# ir-tara-smd-ttp223.net
KiCad netlist of a schematic drawn in Altium Designer
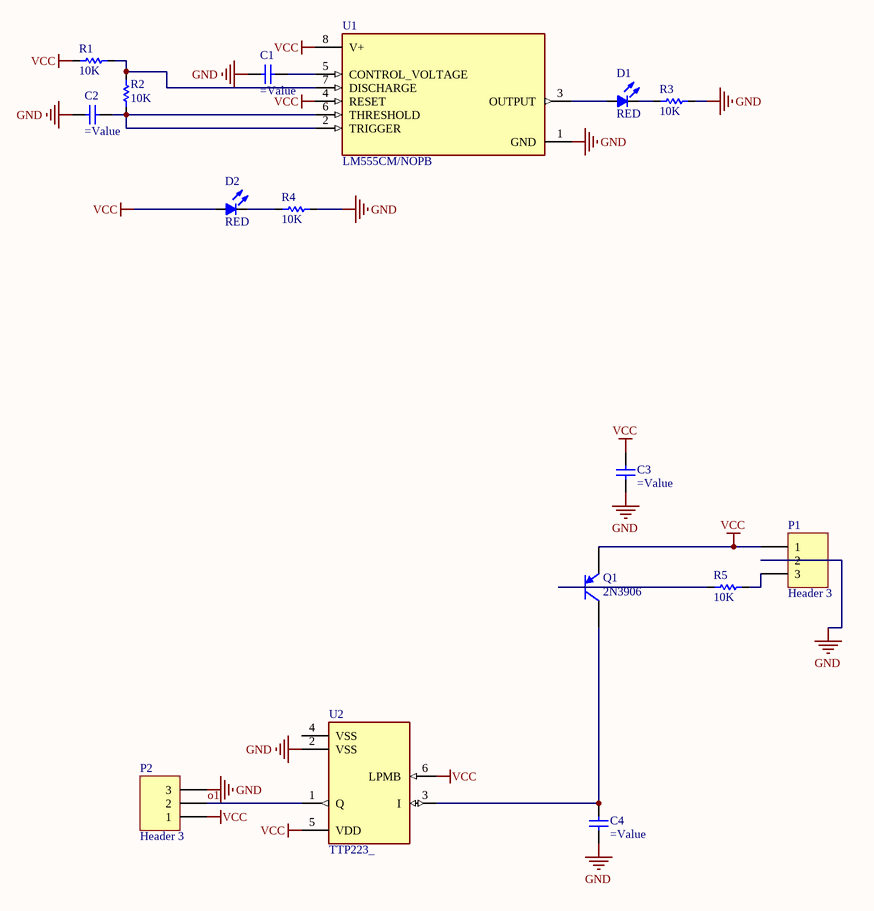
[diagram p0: ir-tara-smd-ttp223.SchDoc]

(export (version "E")
  (design (tool "Eeschema 10.0.6"))
  (components
    (comp (ref "C1")
      (value "~")
      (footprint "CAP 0805")
      (description "Capacitor")
      (libsource (lib "AltiumLib1") (part "Capacitor"))
    )
    (comp (ref "C2")
      (value "~")
      (footprint "CAP 0805")
      (description "Capacitor")
      (libsource (lib "AltiumLib1") (part "Capacitor"))
    )
    (comp (ref "C3")
      (value "~")
      (footprint "CAP 0805")
      (description "Capacitor")
      (libsource (lib "AltiumLib1") (part "Capacitor"))
    )
    (comp (ref "C4")
      (value "~")
      (footprint "CAP 1206")
      (description "Capacitor")
      (libsource (lib "AltiumLib1") (part "Capacitor"))
    )
    (comp (ref "D1")
      (value "MODEL")
      (footprint "LED-5mm")
      (description "Typical LED")
      (fields (field (name "COLOR") "RED"))
      (libsource (lib "AltiumLib1") (part "LED 5mm"))
    )
    (comp (ref "D2")
      (value "MODEL")
      (footprint "LED-5mm")
      (description "Typical LED")
      (fields (field (name "COLOR") "RED"))
      (libsource (lib "AltiumLib1") (part "LED 5mm"))
    )
    (comp (ref "P1")
      (value "Header 3")
      (footprint "HDR1X3")
      (description "Header, 3-Pin")
      (fields (field (name "PUBLISHER") "Altium Limited"))
      (libsource (lib "Miscellaneous Connectors") (part "Header 3"))
    )
    (comp (ref "P2")
      (value "Header 3")
      (footprint "HDR1X3")
      (description "Header, 3-Pin")
      (fields (field (name "PUBLISHER") "Altium Limited"))
      (libsource (lib "") (part "Header 3_1"))
    )
    (comp (ref "Q1")
      (value "2N3906")
      (footprint "MMBT3904-TP:SOT23-3")
      (description "PNP General Purpose Amplifier")
      (fields (field (name "PUBLISHER") "Altium Limited"))
      (libsource (lib "Miscellaneous Devices") (part "2N3906"))
    )
    (comp (ref "R1")
      (value "10K")
      (footprint "RES 0805 (2012X06L)")
      (description "Resistor")
      (fields (field (name "TOLERANCE") "5%") (field (name "POWER") "1/4 W"))
      (libsource (lib "AltiumLib1") (part "Resistor"))
    )
    (comp (ref "R2")
      (value "10K")
      (footprint "RES 0805 (2012X06L)")
      (description "Resistor")
      (fields (field (name "TOLERANCE") "5%") (field (name "POWER") "1/4 W"))
      (libsource (lib "AltiumLib1") (part "Resistor"))
    )
    (comp (ref "R3")
      (value "10K")
      (footprint "RES 0805 (2012X06L)")
      (description "Resistor")
      (fields (field (name "TOLERANCE") "5%") (field (name "POWER") "1/4 W"))
      (libsource (lib "AltiumLib1") (part "Resistor"))
    )
    (comp (ref "R4")
      (value "10K")
      (footprint "RES 1206 (3216X08L)")
      (description "Resistor")
      (fields (field (name "TOLERANCE") "5%") (field (name "POWER") "1/4 W"))
      (libsource (lib "AltiumLib1") (part "Resistor"))
    )
    (comp (ref "R5")
      (value "10K")
      (footprint "RES 0805 (2012X06L)")
      (description "Resistor")
      (fields (field (name "TOLERANCE") "5%") (field (name "POWER") "1/4 W"))
      (libsource (lib "AltiumLib1") (part "Resistor"))
    )
    (comp (ref "U1")
      (value "LM555CM/NOPB")
      (footprint "SOIC127P599X175-8N")
      (description "Highly Stable 555 Timer 8-SOIC 0 to 70")
      (libsource (lib "LM555CM_NOPB") (part "LM555CM/NOPB"))
    )
    (comp (ref "U2")
      (value "TTP223_")
      (footprint "SOT95P285X126-6N")
      (fields (field (name "MP") "TTP223") (field (name "MF") "KOA Speer"))
      (libsource (lib "TTP223_") (part "TTP223_"))
    )
  )
  (nets
    (net (code "1") (name "/o1") (class "Default")
      (node (ref "P2") (pin "2") (pinfunction "2_2") (pintype "passive"))
      (node (ref "U2") (pin "1") (pinfunction "Q_1") (pintype "output"))
    )
    (net (code "2") (name "GND") (class "Default")
      (node (ref "C1") (pin "2") (pinfunction "-_2") (pintype "passive"))
      (node (ref "C2") (pin "2") (pinfunction "-_2") (pintype "passive"))
      (node (ref "C3") (pin "2") (pinfunction "-_2") (pintype "passive"))
      (node (ref "C4") (pin "2") (pinfunction "-_2") (pintype "passive"))
      (node (ref "P1") (pin "2") (pinfunction "2_2") (pintype "passive"))
      (node (ref "P2") (pin "3") (pinfunction "3_3") (pintype "passive"))
      (node (ref "R3") (pin "2") (pinfunction "2_2") (pintype "passive"))
      (node (ref "R4") (pin "2") (pinfunction "2_2") (pintype "passive"))
      (node (ref "U1") (pin "1") (pinfunction "GND_1") (pintype "power_in"))
      (node (ref "U2") (pin "2") (pinfunction "VSS_2") (pintype "power_in"))
    )
    (net (code "3") (name "Net-(C1-+)") (class "Default")
      (node (ref "C1") (pin "1") (pinfunction "+_1") (pintype "passive"))
      (node (ref "U1") (pin "5") (pinfunction "CONTROL_VOLTAGE_5") (pintype "input"))
    )
    (net (code "4") (name "Net-(C2-+)") (class "Default")
      (node (ref "C2") (pin "1") (pinfunction "+_1") (pintype "passive"))
      (node (ref "R2") (pin "1") (pinfunction "1_1") (pintype "passive"))
      (node (ref "U1") (pin "2") (pinfunction "TRIGGER_2") (pintype "input"))
      (node (ref "U1") (pin "6") (pinfunction "THRESHOLD_6") (pintype "input"))
    )
    (net (code "5") (name "Net-(C4-+)") (class "Default")
      (node (ref "C4") (pin "1") (pinfunction "+_1") (pintype "passive"))
      (node (ref "Q1") (pin "3") (pinfunction "C_3") (pintype "passive"))
      (node (ref "U2") (pin "3") (pinfunction "I_3") (pintype "bidirectional"))
    )
    (net (code "6") (name "Net-(D1-A)") (class "Default")
      (node (ref "D1") (pin "1") (pinfunction "A_1") (pintype "passive"))
      (node (ref "U1") (pin "3") (pinfunction "OUTPUT_3") (pintype "output"))
    )
    (net (code "7") (name "Net-(D1-K)") (class "Default")
      (node (ref "D1") (pin "2") (pinfunction "K_2") (pintype "passive"))
      (node (ref "R3") (pin "1") (pinfunction "1_1") (pintype "passive"))
    )
    (net (code "8") (name "Net-(D2-K)") (class "Default")
      (node (ref "D2") (pin "2") (pinfunction "K_2") (pintype "passive"))
      (node (ref "R4") (pin "1") (pinfunction "1_1") (pintype "passive"))
    )
    (net (code "9") (name "Net-(P1-Pad3)") (class "Default")
      (node (ref "P1") (pin "3") (pinfunction "3_3") (pintype "passive"))
      (node (ref "R5") (pin "1") (pinfunction "1_1") (pintype "passive"))
    )
    (net (code "10") (name "Net-(Q1-B)") (class "Default")
      (node (ref "Q1") (pin "2") (pinfunction "B_2") (pintype "passive"))
      (node (ref "R5") (pin "2") (pinfunction "2_2") (pintype "passive"))
    )
    (net (code "11") (name "Net-(U1-DISCHARGE)") (class "Default")
      (node (ref "R1") (pin "1") (pinfunction "1_1") (pintype "passive"))
      (node (ref "R2") (pin "2") (pinfunction "2_2") (pintype "passive"))
      (node (ref "U1") (pin "7") (pinfunction "DISCHARGE_7") (pintype "input"))
    )
    (net (code "12") (name "VCC") (class "Default")
      (node (ref "C3") (pin "1") (pinfunction "+_1") (pintype "passive"))
      (node (ref "D2") (pin "1") (pinfunction "A_1") (pintype "passive"))
      (node (ref "P1") (pin "1") (pinfunction "1_1") (pintype "passive"))
      (node (ref "P2") (pin "1") (pinfunction "1_1") (pintype "passive"))
      (node (ref "Q1") (pin "1") (pinfunction "E_1") (pintype "passive"))
      (node (ref "R1") (pin "2") (pinfunction "2_2") (pintype "passive"))
      (node (ref "U1") (pin "4") (pinfunction "RESET_4") (pintype "input"))
      (node (ref "U1") (pin "8") (pinfunction "V+_8") (pintype "power_in"))
      (node (ref "U2") (pin "5") (pinfunction "VDD_5") (pintype "power_in"))
      (node (ref "U2") (pin "6") (pinfunction "LPMB_6") (pintype "input"))
    )
    (net (code "13") (name "unconnected-(U2-VSS-Pad4)") (class "Default")
      (node (ref "U2") (pin "4") (pinfunction "VSS_4") (pintype "power_in"))
    )
  )
)
